# lm386_nogainctl.net
KiCad netlist of a schematic drawn in EAGLE
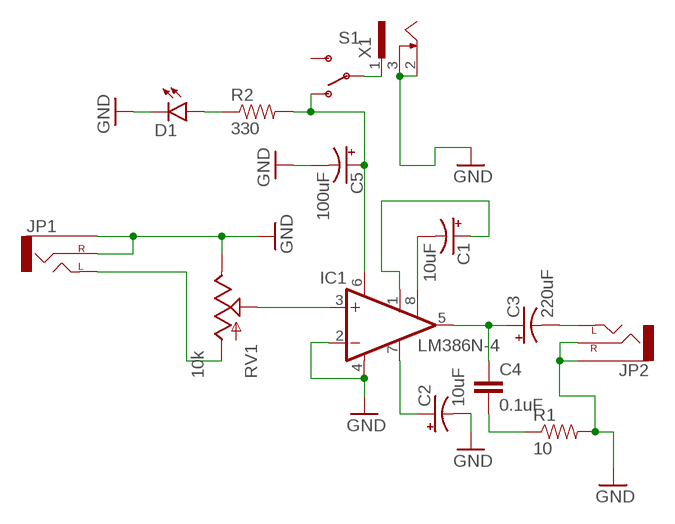
[diagram p0: schematic, sheet 1]

(export (version "E")
  (design (tool "Eeschema 10.0.6"))
  (components
    (comp (ref "C1")
      (value "10uF")
      (footprint "eagle-import:CPOL-RADIAL-10UF-25V")
      (libsource (lib "eagle-import") (part "CAP_POLPTH2"))
    )
    (comp (ref "C2")
      (value "10uF")
      (footprint "eagle-import:CPOL-RADIAL-10UF-25V")
      (libsource (lib "eagle-import") (part "CAP_POLPTH2"))
    )
    (comp (ref "C3")
      (value "220uF")
      (footprint "eagle-import:CPOL-RADIAL-10UF-25V")
      (libsource (lib "eagle-import") (part "CAP_POLPTH2"))
    )
    (comp (ref "C4")
      (value "0.1uF")
      (footprint "eagle-import:CAP-PTH-SMALL2")
      (libsource (lib "eagle-import") (part "CAPPTH2"))
    )
    (comp (ref "C5")
      (value "100uF")
      (footprint "eagle-import:CPOL-RADIAL-100UF-25V")
      (libsource (lib "eagle-import") (part "100UF-25V-20%(PTH)"))
    )
    (comp (ref "D1")
      (value "LED3MM")
      (footprint "eagle-import:LED3MM")
      (libsource (lib "eagle-import") (part "LED3MM"))
    )
    (comp (ref "IC1")
      (value "LM386N-4")
      (footprint "eagle-import:DIL08")
      (libsource (lib "eagle-import") (part "LM386?-N4"))
    )
    (comp (ref "JP1")
      (value "AUDIO-JACKPTH")
      (footprint "eagle-import:AUDIO-JACK")
      (libsource (lib "eagle-import") (part "AUDIO-JACKPTH"))
    )
    (comp (ref "JP2")
      (value "AUDIO-JACKPTH")
      (footprint "eagle-import:AUDIO-JACK")
      (libsource (lib "eagle-import") (part "AUDIO-JACKPTH"))
    )
    (comp (ref "R1")
      (value "10")
      (footprint "eagle-import:AXIAL-0.4")
      (libsource (lib "eagle-import") (part "RESISTORPTH-1/4W"))
    )
    (comp (ref "R2")
      (value "330")
      (footprint "eagle-import:AXIAL-0.4")
      (libsource (lib "eagle-import") (part "SparkFun-Resistors_RESISTORPTH-1/4W"))
    )
    (comp (ref "RV1")
      (value "10k")
      (footprint "eagle-import:ALPS_POT")
      (libsource (lib "eagle-import") (part "POT"))
    )
    (comp (ref "S1")
      (value "SWITCH-SPDTPTH_LOCK")
      (footprint "eagle-import:SWITCH-SPDT_LOCK.007S")
      (libsource (lib "eagle-import") (part "SWITCH-SPDTPTH_LOCK"))
    )
    (comp (ref "X1")
      (value "SCD-014A")
      (footprint "eagle-import:SCD-014-A")
      (libsource (lib "eagle-import") (part "SCD-014A"))
    )
  )
  (nets
    (net (code "1") (name "GND") (class "Default")
      (node (ref "C2") (pin "2") (pinfunction "-_2") (pintype "passive"))
      (node (ref "C5") (pin "2") (pinfunction "-_2") (pintype "passive"))
      (node (ref "D1") (pin "K") (pinfunction "C_K") (pintype "passive"))
      (node (ref "IC1") (pin "2") (pinfunction "-IN_2") (pintype "input"))
      (node (ref "IC1") (pin "4") (pinfunction "GND_4") (pintype "power_in"))
      (node (ref "JP1") (pin "RING") (pinfunction "RIGHT_RING") (pintype "bidirectional"))
      (node (ref "JP1") (pin "SLEEVE") (pinfunction "SLEEVE_SLEEVE") (pintype "bidirectional"))
      (node (ref "JP2") (pin "RING") (pinfunction "RIGHT_RING") (pintype "bidirectional"))
      (node (ref "JP2") (pin "SLEEVE") (pinfunction "SLEEVE_SLEEVE") (pintype "bidirectional"))
      (node (ref "R1") (pin "P$2") (pinfunction "2_P$2") (pintype "passive"))
      (node (ref "RV1") (pin "P$1") (pinfunction "E_P$1") (pintype "passive"))
      (node (ref "X1") (pin "2") (pinfunction "2_2") (pintype "passive"))
      (node (ref "X1") (pin "3") (pinfunction "3_3") (pintype "passive"))
    )
    (net (code "2") (name "Net-(C1-+)") (class "Default")
      (node (ref "C1") (pin "1") (pinfunction "+_1") (pintype "passive"))
      (node (ref "IC1") (pin "1") (pinfunction "GAIN_1") (pintype "passive"))
    )
    (net (code "3") (name "Net-(C1--)") (class "Default")
      (node (ref "C1") (pin "2") (pinfunction "-_2") (pintype "passive"))
      (node (ref "IC1") (pin "8") (pinfunction "GAIN_8") (pintype "passive"))
    )
    (net (code "4") (name "Net-(C2-+)") (class "Default")
      (node (ref "C2") (pin "1") (pinfunction "+_1") (pintype "passive"))
      (node (ref "IC1") (pin "7") (pinfunction "BYPASS_7") (pintype "passive"))
    )
    (net (code "5") (name "Net-(C3-+)") (class "Default")
      (node (ref "C3") (pin "1") (pinfunction "+_1") (pintype "passive"))
      (node (ref "C4") (pin "1") (pinfunction "1_1") (pintype "passive"))
      (node (ref "IC1") (pin "5") (pinfunction "OUT_5") (pintype "output"))
    )
    (net (code "6") (name "Net-(C3--)") (class "Default")
      (node (ref "C3") (pin "2") (pinfunction "-_2") (pintype "passive"))
      (node (ref "JP2") (pin "TIP") (pinfunction "LEFT_TIP") (pintype "bidirectional"))
    )
    (net (code "7") (name "Net-(C5-+)") (class "Default")
      (node (ref "C5") (pin "1") (pinfunction "+_1") (pintype "passive"))
      (node (ref "IC1") (pin "6") (pinfunction "VS_6") (pintype "power_in"))
      (node (ref "R2") (pin "P$2") (pinfunction "2_P$2") (pintype "passive"))
      (node (ref "S1") (pin "1") (pinfunction "O_1") (pintype "passive"))
    )
    (net (code "8") (name "Net-(IC1-+IN)") (class "Default")
      (node (ref "IC1") (pin "3") (pinfunction "+IN_3") (pintype "input"))
      (node (ref "RV1") (pin "P$2") (pinfunction "S_P$2") (pintype "passive"))
    )
    (net (code "9") (name "Net-(JP1-LEFT)") (class "Default")
      (node (ref "JP1") (pin "TIP") (pinfunction "LEFT_TIP") (pintype "bidirectional"))
      (node (ref "RV1") (pin "P$3") (pinfunction "A_P$3") (pintype "passive"))
    )
    (net (code "10") (name "Net-(R1-1)") (class "Default")
      (node (ref "C4") (pin "2") (pinfunction "2_2") (pintype "passive"))
      (node (ref "R1") (pin "P$1") (pinfunction "1_P$1") (pintype "passive"))
    )
    (net (code "11") (name "Net-(R2-1)") (class "Default")
      (node (ref "D1") (pin "A") (pinfunction "A_A") (pintype "passive"))
      (node (ref "R2") (pin "P$1") (pinfunction "1_P$1") (pintype "passive"))
    )
    (net (code "12") (name "Net-(S1-P)") (class "Default")
      (node (ref "S1") (pin "2") (pinfunction "P_2") (pintype "passive"))
      (node (ref "X1") (pin "1") (pinfunction "1_1") (pintype "passive"))
    )
    (net (code "13") (name "unconnected-(S1-S-Pad3)") (class "Default")
      (node (ref "S1") (pin "3") (pinfunction "S_3") (pintype "passive"))
    )
  )
)
